# samd21_actuatorhub_Lite_TQFP32_1_1_2Feb_.net
KiCad netlist of a schematic drawn in EAGLE
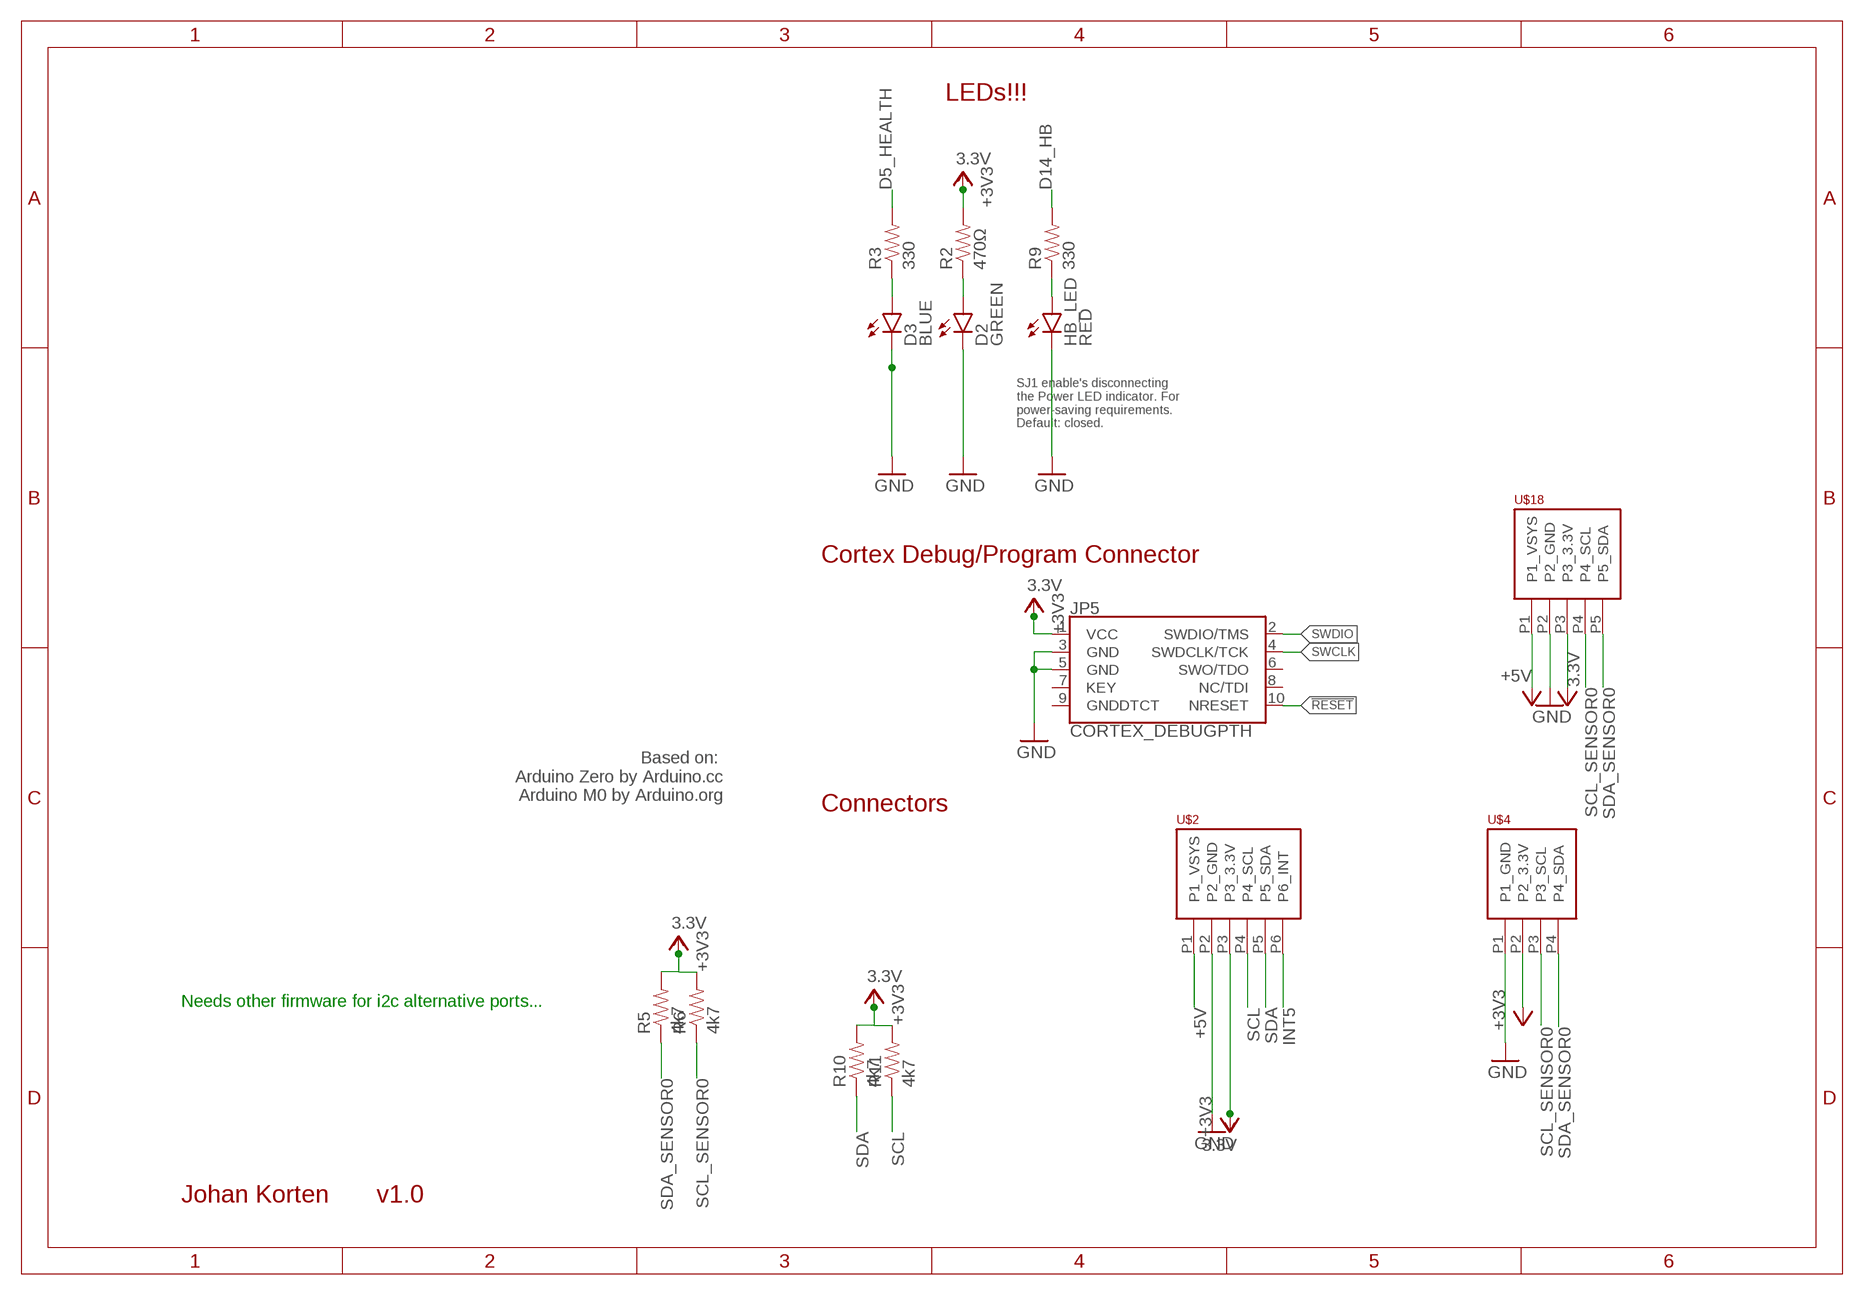
[diagram p0: schematic, sheet 1]
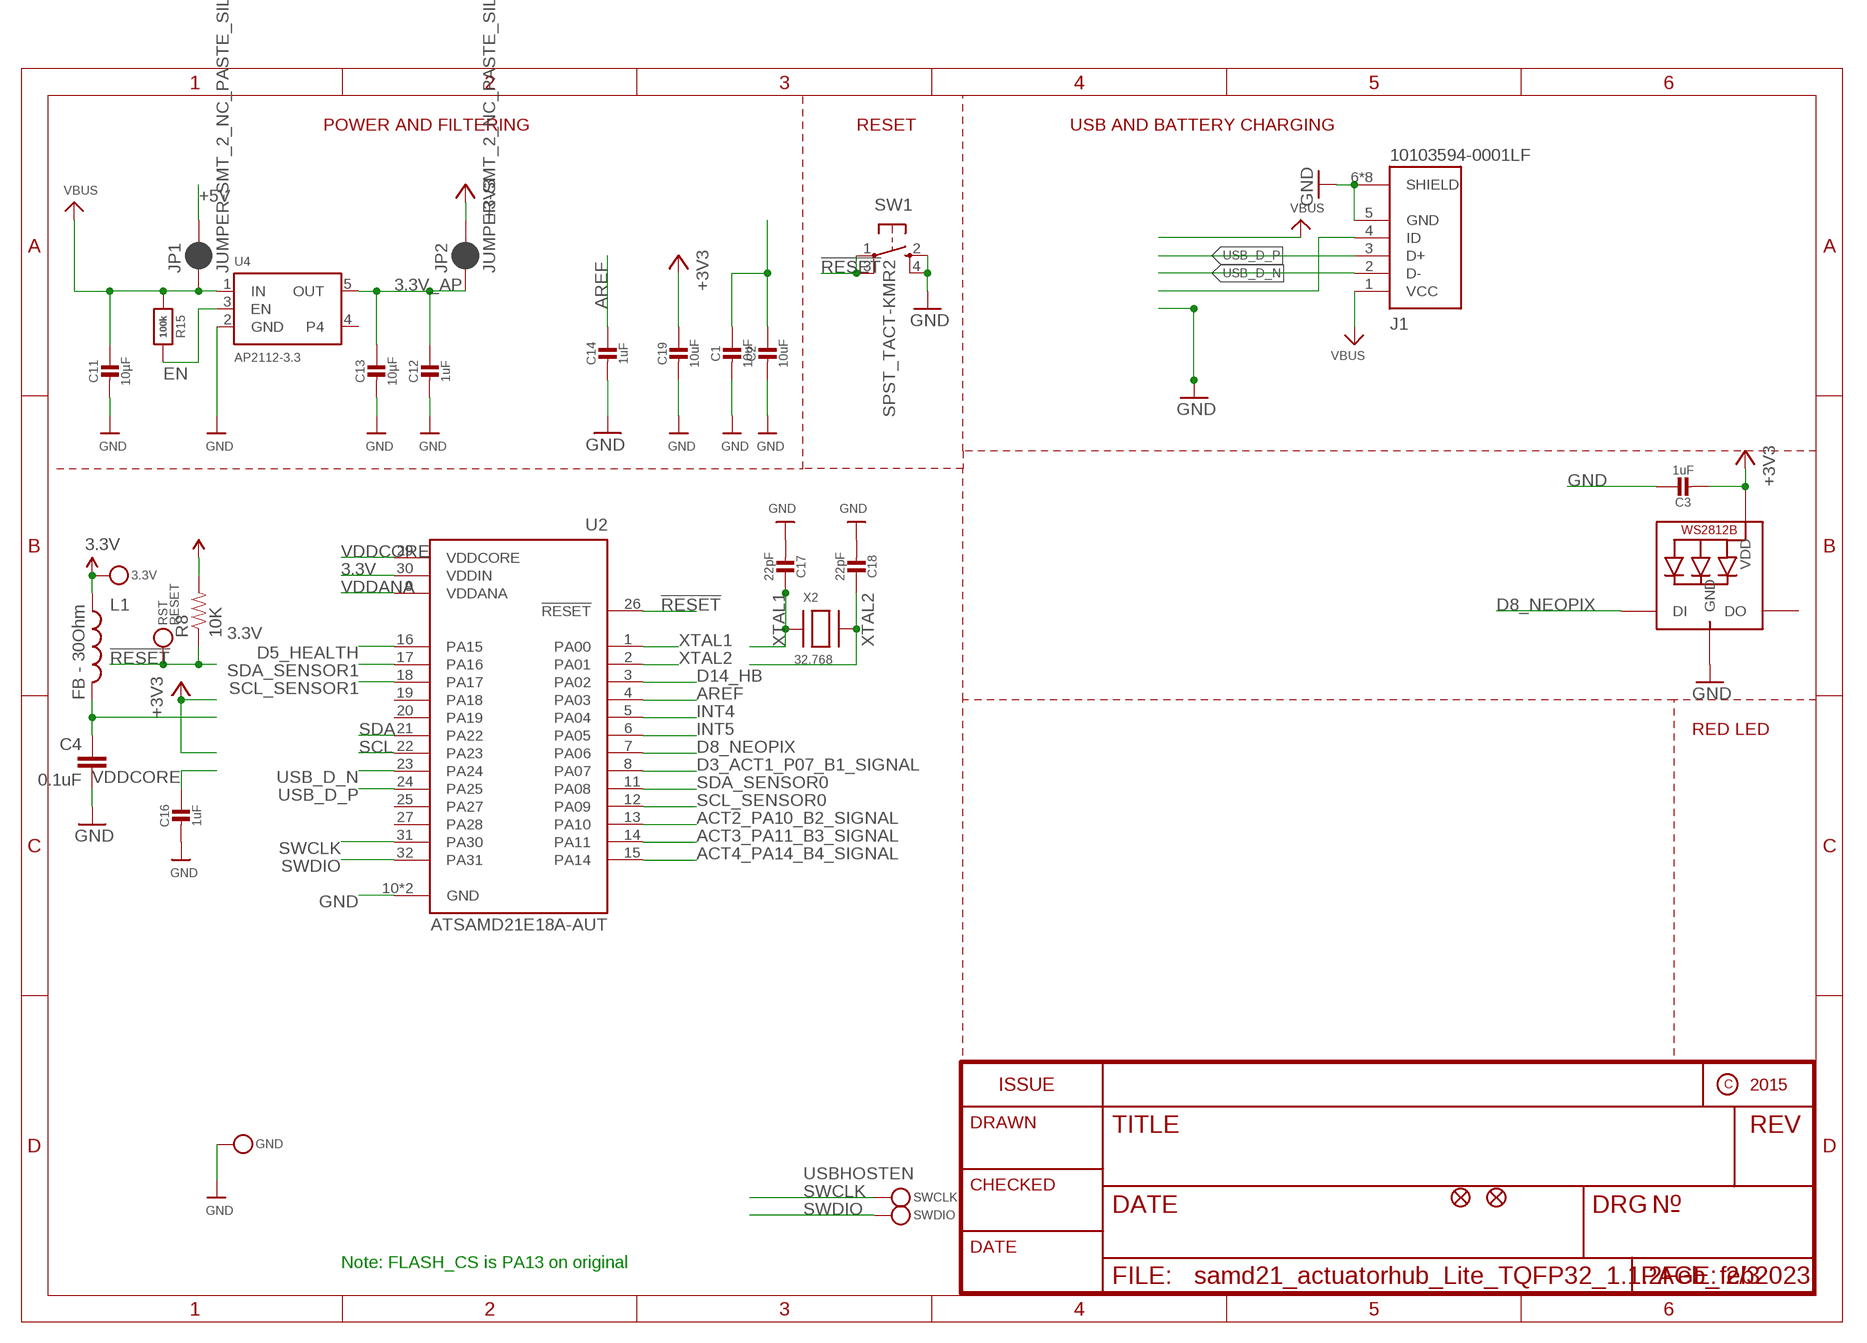
[diagram p1: schematic, sheet 2]
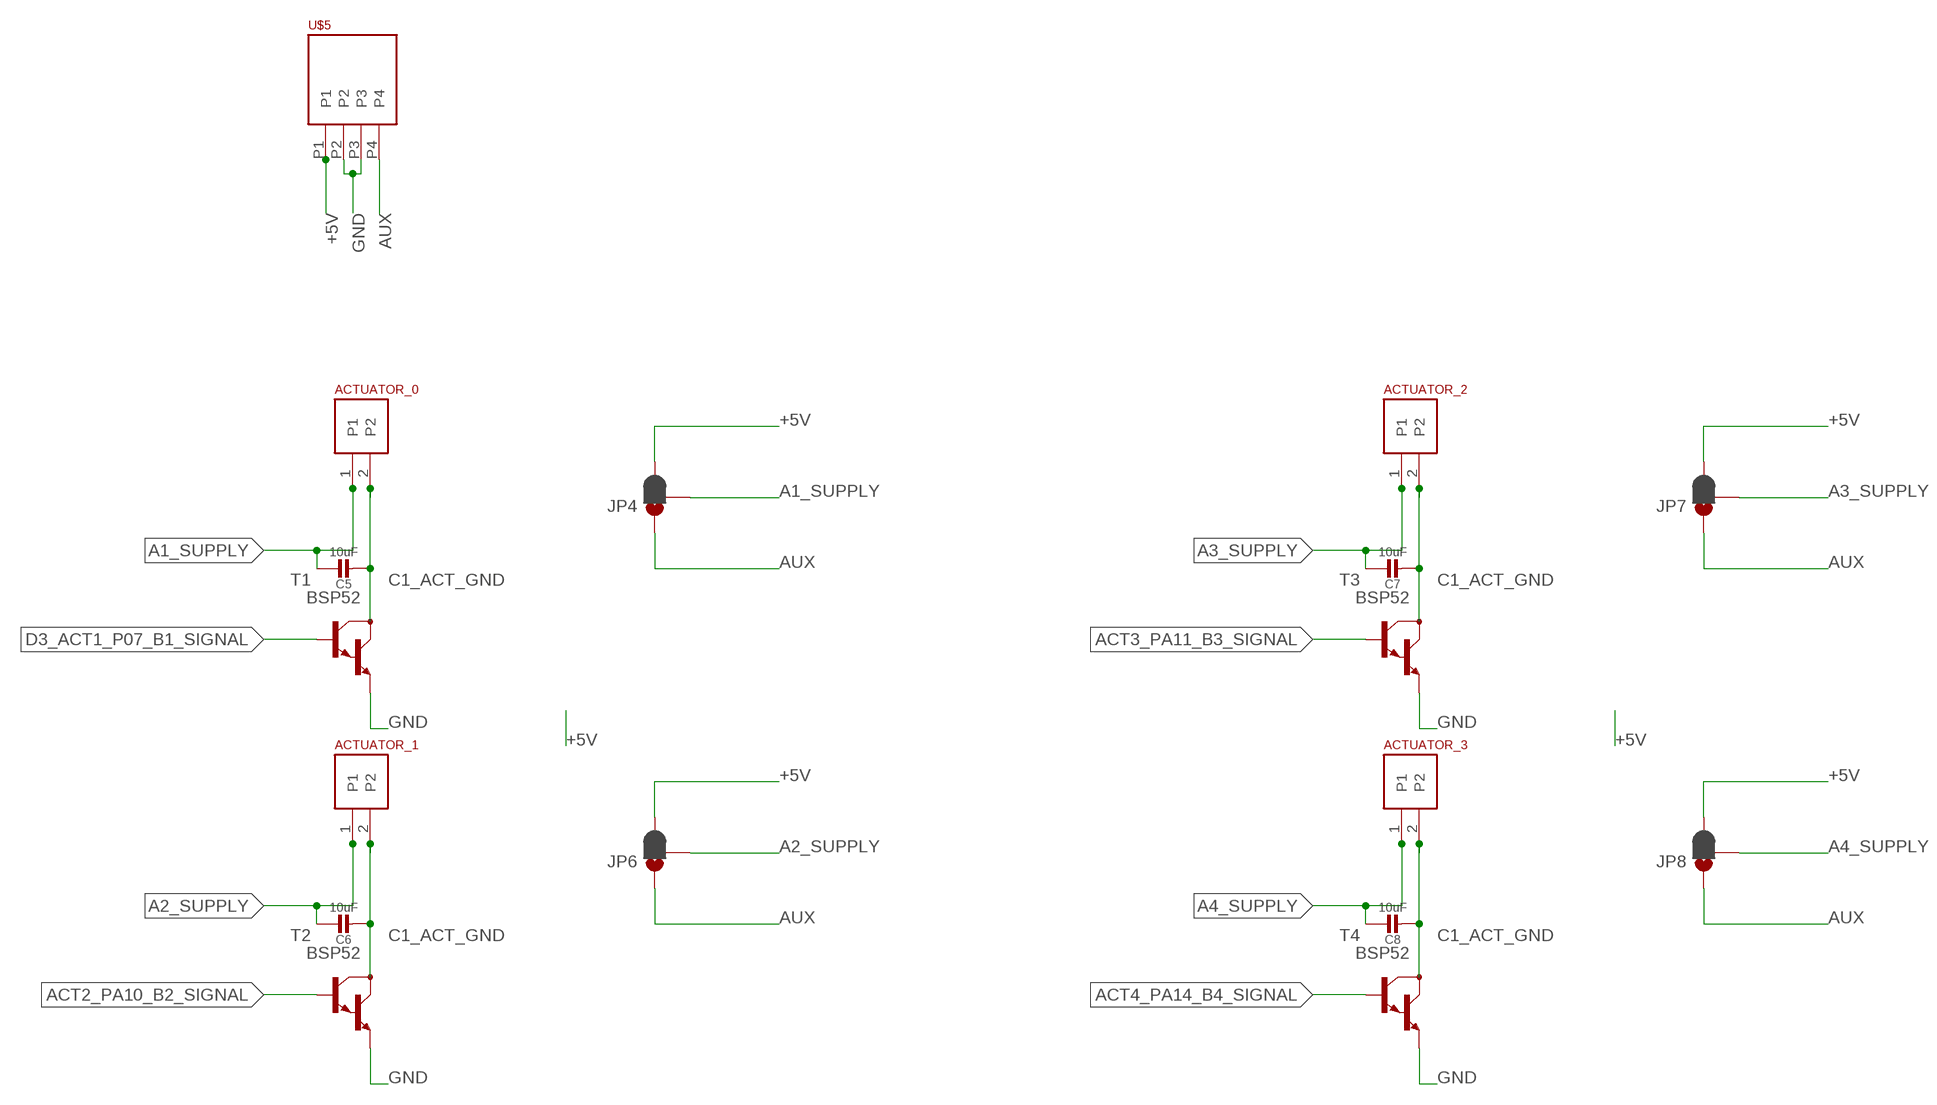
[diagram p2: schematic, sheet 3]

(export (version "E")
  (design (tool "Eeschema 10.0.6"))
  (components
    (comp (ref "ACTUATOR_0")
      (value "PHOENIX_PTSM_M2TH")
      (footprint "eagle-import:PTSM_M2_THRHOLE")
      (libsource (lib "eagle-import") (part "PHOENIX_PTSM_M2TH"))
    )
    (comp (ref "ACTUATOR_1")
      (value "PHOENIX_PTSM_M2TH")
      (footprint "eagle-import:PTSM_M2_THRHOLE")
      (libsource (lib "eagle-import") (part "PHOENIX_PTSM_M2TH"))
    )
    (comp (ref "ACTUATOR_2")
      (value "PHOENIX_PTSM_M2TH")
      (footprint "eagle-import:PTSM_M2_THRHOLE")
      (libsource (lib "eagle-import") (part "PHOENIX_PTSM_M2TH"))
    )
    (comp (ref "ACTUATOR_3")
      (value "PHOENIX_PTSM_M2TH")
      (footprint "eagle-import:PTSM_M2_THRHOLE")
      (libsource (lib "eagle-import") (part "PHOENIX_PTSM_M2TH"))
    )
    (comp (ref "C5")
      (value "10uF")
      (footprint "eagle-import:0805-NO")
      (libsource (lib "eagle-import") (part "CAP_CERAMIC0805-NOOUTLINE"))
    )
    (comp (ref "C6")
      (value "10uF")
      (footprint "eagle-import:0805-NO")
      (libsource (lib "eagle-import") (part "CAP_CERAMIC0805-NOOUTLINE"))
    )
    (comp (ref "C7")
      (value "10uF")
      (footprint "eagle-import:0805-NO")
      (libsource (lib "eagle-import") (part "CAP_CERAMIC0805-NOOUTLINE"))
    )
    (comp (ref "C8")
      (value "10uF")
      (footprint "eagle-import:0805-NO")
      (libsource (lib "eagle-import") (part "CAP_CERAMIC0805-NOOUTLINE"))
    )
    (comp (ref "JP4")
      (value "JUMPER-SMT_3_1-NC_PASTE_SILK")
      (footprint "eagle-import:SMT-JUMPER_3_1-NC_PASTE_SILK")
      (libsource (lib "eagle-import") (part "JUMPER-SMT_3_1-NC_PASTE_SILK"))
    )
    (comp (ref "JP6")
      (value "JUMPER-SMT_3_1-NC_PASTE_SILK")
      (footprint "eagle-import:SMT-JUMPER_3_1-NC_PASTE_SILK")
      (libsource (lib "eagle-import") (part "JUMPER-SMT_3_1-NC_PASTE_SILK"))
    )
    (comp (ref "JP7")
      (value "JUMPER-SMT_3_1-NC_PASTE_SILK")
      (footprint "eagle-import:SMT-JUMPER_3_1-NC_PASTE_SILK")
      (libsource (lib "eagle-import") (part "JUMPER-SMT_3_1-NC_PASTE_SILK"))
    )
    (comp (ref "JP8")
      (value "JUMPER-SMT_3_1-NC_PASTE_SILK")
      (footprint "eagle-import:SMT-JUMPER_3_1-NC_PASTE_SILK")
      (libsource (lib "eagle-import") (part "JUMPER-SMT_3_1-NC_PASTE_SILK"))
    )
    (comp (ref "T1")
      (value "BSP52")
      (footprint "eagle-import:SOT-223-4")
      (fields (field (name "MF") "ON Semiconductor"))
      (libsource (lib "eagle-import") (part "BSP52"))
    )
    (comp (ref "T2")
      (value "BSP52")
      (footprint "eagle-import:SOT-223-4")
      (fields (field (name "MF") "ON Semiconductor"))
      (libsource (lib "eagle-import") (part "BSP52"))
    )
    (comp (ref "T3")
      (value "BSP52")
      (footprint "eagle-import:SOT-223-4")
      (fields (field (name "MF") "ON Semiconductor"))
      (libsource (lib "eagle-import") (part "BSP52"))
    )
    (comp (ref "T4")
      (value "BSP52")
      (footprint "eagle-import:SOT-223-4")
      (fields (field (name "MF") "ON Semiconductor"))
      (libsource (lib "eagle-import") (part "BSP52"))
    )
    (comp (ref "U$5")
      (value "PHOENIX_PTSM_M4_TH_ANGLE")
      (footprint "eagle-import:PTSM_M4_TH_ANGLE_NEUTRAL")
      (libsource (lib "eagle-import") (part "PHOENIX_PTSM_M4_TH_ANGLE"))
    )
    (comp (ref "D2")
      (value "GREEN")
      (footprint "eagle-import:LED-0603")
      (libsource (lib "eagle-import") (part "LED-RED0603"))
    )
    (comp (ref "D3")
      (value "BLUE")
      (footprint "eagle-import:LED-0603")
      (libsource (lib "eagle-import") (part "LED-BLUE0603"))
    )
    (comp (ref "HB_LED")
      (value "RED")
      (footprint "eagle-import:LED-0603")
      (libsource (lib "eagle-import") (part "LED-RED0603"))
    )
    (comp (ref "JP5")
      (value "CORTEX_DEBUGPTH")
      (footprint "eagle-import:2X5-PTH-1.27MM")
      (libsource (lib "eagle-import") (part "CORTEX_DEBUGPTH"))
    )
    (comp (ref "R2")
      (value "470Ω")
      (footprint "eagle-import:0603-RES")
      (libsource (lib "eagle-import") (part "330OHM1/10W1%(0603)"))
    )
    (comp (ref "R3")
      (value "330")
      (footprint "eagle-import:0603-RES")
      (libsource (lib "eagle-import") (part "330OHM1/10W1%(0603)"))
    )
    (comp (ref "R5")
      (value "4k7")
      (footprint "eagle-import:0603-RES")
      (libsource (lib "eagle-import") (part "330OHM1/10W1%(0603)"))
    )
    (comp (ref "R6")
      (value "4k7")
      (footprint "eagle-import:0603-RES")
      (libsource (lib "eagle-import") (part "330OHM1/10W1%(0603)"))
    )
    (comp (ref "R9")
      (value "330")
      (footprint "eagle-import:0603-RES")
      (libsource (lib "eagle-import") (part "330OHM1/10W1%(0603)"))
    )
    (comp (ref "R10")
      (value "4k7")
      (footprint "eagle-import:0603-RES")
      (libsource (lib "eagle-import") (part "330OHM1/10W1%(0603)"))
    )
    (comp (ref "R11")
      (value "4k7")
      (footprint "eagle-import:0603-RES")
      (libsource (lib "eagle-import") (part "330OHM1/10W1%(0603)"))
    )
    (comp (ref "U$2")
      (value "PHOENIX_PTSM_M6_TH_I2CPPANGLE")
      (footprint "eagle-import:PTSM_M6_THRHOLE")
      (libsource (lib "eagle-import") (part "PHOENIX_PTSM_M6_TH_I2CPPANGLE"))
    )
    (comp (ref "U$4")
      (value "PHOENIX_PTSM_M4_THANGLE")
      (footprint "eagle-import:PTSM_M4_TH")
      (libsource (lib "eagle-import") (part "PHOENIX_PTSM_M4_THANGLE"))
    )
    (comp (ref "U$18")
      (value "PHOENIX_PTSM_M5_TH_I2C++")
      (footprint "eagle-import:PTSM_M5_THRHOLE")
      (libsource (lib "eagle-import") (part "PHOENIX_PTSM_M5_TH_I2C++"))
    )
    (comp (ref "3.3V")
      (value "TESTPOINTROUND1.5MM")
      (footprint "eagle-import:TESTPOINT_ROUND_1.5MM")
      (libsource (lib "eagle-import") (part "TESTPOINTROUND1.5MM"))
    )
    (comp (ref "C1")
      (value "10uF")
      (footprint "eagle-import:0805-NO")
      (libsource (lib "eagle-import") (part "CAP_CERAMIC0805-NOOUTLINE"))
    )
    (comp (ref "C2")
      (value "10uF")
      (footprint "eagle-import:0805-NO")
      (libsource (lib "eagle-import") (part "CAP_CERAMIC0805-NOOUTLINE"))
    )
    (comp (ref "C3")
      (value "1uF")
      (footprint "eagle-import:0603-NO")
      (libsource (lib "eagle-import") (part "CAP_CERAMIC0603_NO"))
    )
    (comp (ref "C4")
      (value "0.1uF")
      (footprint "eagle-import:0402-CAP")
      (libsource (lib "eagle-import") (part "0.1UF-16V(+-10%)(0402)"))
    )
    (comp (ref "C11")
      (value "10µF")
      (footprint "eagle-import:0805-NO")
      (libsource (lib "eagle-import") (part "CAP_CERAMIC0805-NOOUTLINE"))
    )
    (comp (ref "C12")
      (value "1uF")
      (footprint "eagle-import:0603-NO")
      (libsource (lib "eagle-import") (part "CAP_CERAMIC0603_NO"))
    )
    (comp (ref "C13")
      (value "10µF")
      (footprint "eagle-import:0805-NO")
      (libsource (lib "eagle-import") (part "CAP_CERAMIC0805-NOOUTLINE"))
    )
    (comp (ref "C14")
      (value "1uF")
      (footprint "eagle-import:0603-NO")
      (libsource (lib "eagle-import") (part "CAP_CERAMIC0603_NO"))
    )
    (comp (ref "C16")
      (value "1uF")
      (footprint "eagle-import:0603-NO")
      (libsource (lib "eagle-import") (part "CAP_CERAMIC0603_NO"))
    )
    (comp (ref "C17")
      (value "22pF")
      (footprint "eagle-import:0603-NO")
      (libsource (lib "eagle-import") (part "CAP_CERAMIC0603_NO"))
    )
    (comp (ref "C18")
      (value "22pF")
      (footprint "eagle-import:0603-NO")
      (libsource (lib "eagle-import") (part "CAP_CERAMIC0603_NO"))
    )
    (comp (ref "C19")
      (value "10uF")
      (footprint "eagle-import:0805-NO")
      (libsource (lib "eagle-import") (part "CAP_CERAMIC0805-NOOUTLINE"))
    )
    (comp (ref "GND")
      (value "TESTPOINTROUND1.5MM")
      (footprint "eagle-import:TESTPOINT_ROUND_1.5MM")
      (libsource (lib "eagle-import") (part "TESTPOINTROUND1.5MM"))
    )
    (comp (ref "J1")
      (value "10103594-0001LF")
      (footprint "eagle-import:AMPHENOL_10103594-0001LF")
      (fields (field (name "MF") "AMPHENOL ICC / FCI"))
      (libsource (lib "eagle-import") (part "10103594-0001LF"))
    )
    (comp (ref "JP1")
      (value "JUMPER-SMT_2_NC_PASTE_SILK")
      (footprint "eagle-import:SMT-JUMPER_2_NC_PASTE_SILK")
      (libsource (lib "eagle-import") (part "JUMPER-SMT_2_NC_PASTE_SILK"))
    )
    (comp (ref "JP2")
      (value "JUMPER-SMT_2_NC_PASTE_SILK")
      (footprint "eagle-import:SMT-JUMPER_2_NC_PASTE_SILK")
      (libsource (lib "eagle-import") (part "JUMPER-SMT_2_NC_PASTE_SILK"))
    )
    (comp (ref "L1")
      (value "FB - 30Ohm")
      (footprint "eagle-import:0603")
      (libsource (lib "eagle-import") (part "INDUCTOR0603"))
    )
    (comp (ref "LED1")
      (value "WS2812B3535")
      (footprint "eagle-import:LED3535")
      (libsource (lib "eagle-import") (part "WS2812B3535"))
    )
    (comp (ref "R8")
      (value "10K")
      (footprint "eagle-import:0603-RES")
      (libsource (lib "eagle-import") (part "10KOHM-1/10W-1%(0603)0603"))
    )
    (comp (ref "R15")
      (value "100k")
      (footprint "eagle-import:0603-NO")
      (libsource (lib "eagle-import") (part "RESISTOR_0603_NOOUT"))
    )
    (comp (ref "RST")
      (value "RESET")
      (footprint "eagle-import:TESTPOINT_ROUND_1.5MM")
      (libsource (lib "eagle-import") (part "TESTPOINTROUND1.5MM"))
    )
    (comp (ref "SW1")
      (value "SPST_TACT-KMR2")
      (footprint "eagle-import:KMR2")
      (libsource (lib "eagle-import") (part "SPST_TACT-KMR2"))
    )
    (comp (ref "SWCLK")
      (value "TESTPOINTROUND1.5MM")
      (footprint "eagle-import:TESTPOINT_ROUND_1.5MM")
      (libsource (lib "eagle-import") (part "TESTPOINTROUND1.5MM"))
    )
    (comp (ref "SWDIO")
      (value "TESTPOINTROUND1.5MM")
      (footprint "eagle-import:TESTPOINT_ROUND_1.5MM")
      (libsource (lib "eagle-import") (part "TESTPOINTROUND1.5MM"))
    )
    (comp (ref "U$34")
      (value "FIDUCIAL\"\"")
      (footprint "eagle-import:FIDUCIAL_1MM")
      (libsource (lib "eagle-import") (part "FIDUCIAL{dblquote}{dblquote}"))
    )
    (comp (ref "U$35")
      (value "FIDUCIAL\"\"")
      (footprint "eagle-import:FIDUCIAL_1MM")
      (libsource (lib "eagle-import") (part "FIDUCIAL{dblquote}{dblquote}"))
    )
    (comp (ref "U2")
      (value "ATSAMD21E18A-AUT")
      (footprint "eagle-import:QFP80P900X900X120-32N")
      (fields (field (name "MF") "Microchip") (field (name "MP") "ATSAMD21E18A-AU"))
      (libsource (lib "eagle-import") (part "ATSAMD21E18A-AUT"))
    )
    (comp (ref "U4")
      (value "AP2112-3.3")
      (footprint "eagle-import:SOT23-5")
      (libsource (lib "eagle-import") (part "VREG_SOT23-5"))
    )
    (comp (ref "X2")
      (value "32.768")
      (footprint "eagle-import:XTAL3215")
      (libsource (lib "eagle-import") (part "XTAL-3.2X1.5"))
    )
  )
  (nets
    (net (code "1") (name "+5V") (class "Default")
      (node (ref "C1") (pin "1") (pinfunction "1_1") (pintype "passive"))
      (node (ref "C2") (pin "1") (pinfunction "1_1") (pintype "passive"))
      (node (ref "JP1") (pin "2") (pinfunction "2_2") (pintype "passive"))
      (node (ref "JP4") (pin "3") (pinfunction "3_3") (pintype "passive"))
      (node (ref "JP6") (pin "3") (pinfunction "3_3") (pintype "passive"))
      (node (ref "JP7") (pin "3") (pinfunction "3_3") (pintype "passive"))
      (node (ref "JP8") (pin "3") (pinfunction "3_3") (pintype "passive"))
      (node (ref "U$18") (pin "P1") (pinfunction "P1_VSYS_P1") (pintype "power_in"))
      (node (ref "U$2") (pin "P1") (pinfunction "P1_VSYS_P1") (pintype "power_in"))
      (node (ref "U$5") (pin "P1") (pinfunction "P1_P1") (pintype "power_in"))
    )
    (net (code "2") (name "3.3V") (class "Default")
      (node (ref "3.3V") (pin "P$1") (pinfunction "P$1_P$1") (pintype "bidirectional"))
      (node (ref "C19") (pin "1") (pinfunction "1_1") (pintype "passive"))
      (node (ref "C3") (pin "2") (pinfunction "2_2") (pintype "passive"))
      (node (ref "JP2") (pin "2") (pinfunction "2_2") (pintype "passive"))
      (node (ref "JP5") (pin "1") (pinfunction "VCC_1") (pintype "bidirectional"))
      (node (ref "L1") (pin "1") (pinfunction "1_1") (pintype "passive"))
      (node (ref "LED1") (pin "2") (pinfunction "VDD_2") (pintype "power_in"))
      (node (ref "R10") (pin "2") (pinfunction "2_2") (pintype "passive"))
      (node (ref "R11") (pin "2") (pinfunction "2_2") (pintype "passive"))
      (node (ref "R2") (pin "2") (pinfunction "2_2") (pintype "passive"))
      (node (ref "R5") (pin "2") (pinfunction "2_2") (pintype "passive"))
      (node (ref "R6") (pin "2") (pinfunction "2_2") (pintype "passive"))
      (node (ref "R8") (pin "2") (pinfunction "2_2") (pintype "passive"))
      (node (ref "U$18") (pin "P3") (pinfunction "P3_3.3V_P3") (pintype "power_in"))
      (node (ref "U$2") (pin "P3") (pinfunction "P3_3.3V_P3") (pintype "power_in"))
      (node (ref "U$4") (pin "P2") (pinfunction "P2_3.3V_P2") (pintype "power_in"))
      (node (ref "U2") (pin "30") (pinfunction "VDDIN_30") (pintype "power_in"))
    )
    (net (code "3") (name "3.3V_AP") (class "Default")
      (node (ref "C12") (pin "1") (pinfunction "1_1") (pintype "passive"))
      (node (ref "C13") (pin "1") (pinfunction "1_1") (pintype "passive"))
      (node (ref "JP2") (pin "1") (pinfunction "1_1") (pintype "passive"))
      (node (ref "U4") (pin "5") (pinfunction "OUT_5") (pintype "power_in"))
    )
    (net (code "4") (name "A1_SUPPLY") (class "Default")
      (node (ref "ACTUATOR_0") (pin "1") (pinfunction "P1_1") (pintype "bidirectional"))
      (node (ref "C5") (pin "1") (pinfunction "1_1") (pintype "passive"))
      (node (ref "JP4") (pin "2") (pinfunction "2_2") (pintype "passive"))
    )
    (net (code "5") (name "A2_SUPPLY") (class "Default")
      (node (ref "ACTUATOR_1") (pin "1") (pinfunction "P1_1") (pintype "bidirectional"))
      (node (ref "C6") (pin "1") (pinfunction "1_1") (pintype "passive"))
      (node (ref "JP6") (pin "2") (pinfunction "2_2") (pintype "passive"))
    )
    (net (code "6") (name "A3_SUPPLY") (class "Default")
      (node (ref "ACTUATOR_2") (pin "1") (pinfunction "P1_1") (pintype "bidirectional"))
      (node (ref "C7") (pin "1") (pinfunction "1_1") (pintype "passive"))
      (node (ref "JP7") (pin "2") (pinfunction "2_2") (pintype "passive"))
    )
    (net (code "7") (name "A4_SUPPLY") (class "Default")
      (node (ref "ACTUATOR_3") (pin "1") (pinfunction "P1_1") (pintype "bidirectional"))
      (node (ref "C8") (pin "1") (pinfunction "1_1") (pintype "passive"))
      (node (ref "JP8") (pin "2") (pinfunction "2_2") (pintype "passive"))
    )
    (net (code "8") (name "ACT2_PA10_B2_SIGNAL") (class "Default")
      (node (ref "T2") (pin "1") (pinfunction "B_1") (pintype "passive"))
      (node (ref "U2") (pin "13") (pinfunction "PA10_13") (pintype "bidirectional"))
    )
    (net (code "9") (name "ACT3_PA11_B3_SIGNAL") (class "Default")
      (node (ref "T3") (pin "1") (pinfunction "B_1") (pintype "passive"))
      (node (ref "U2") (pin "14") (pinfunction "PA11_14") (pintype "bidirectional"))
    )
    (net (code "10") (name "ACT4_PA14_B4_SIGNAL") (class "Default")
      (node (ref "T4") (pin "1") (pinfunction "B_1") (pintype "passive"))
      (node (ref "U2") (pin "15") (pinfunction "PA14_15") (pintype "bidirectional"))
    )
    (net (code "11") (name "AREF") (class "Default")
      (node (ref "C14") (pin "1") (pinfunction "1_1") (pintype "passive"))
      (node (ref "U2") (pin "4") (pinfunction "PA03_4") (pintype "bidirectional"))
    )
    (net (code "12") (name "AUX") (class "Default")
      (node (ref "JP4") (pin "1") (pinfunction "1_1") (pintype "passive"))
      (node (ref "JP6") (pin "1") (pinfunction "1_1") (pintype "passive"))
      (node (ref "JP7") (pin "1") (pinfunction "1_1") (pintype "passive"))
      (node (ref "JP8") (pin "1") (pinfunction "1_1") (pintype "passive"))
      (node (ref "U$5") (pin "P4") (pinfunction "P4_P4") (pintype "power_in"))
    )
    (net (code "13") (name "C1_ACT_GND") (class "Default")
      (node (ref "ACTUATOR_0") (pin "2") (pinfunction "P2_2") (pintype "bidirectional"))
      (node (ref "ACTUATOR_1") (pin "2") (pinfunction "P2_2") (pintype "bidirectional"))
      (node (ref "ACTUATOR_2") (pin "2") (pinfunction "P2_2") (pintype "bidirectional"))
      (node (ref "ACTUATOR_3") (pin "2") (pinfunction "P2_2") (pintype "bidirectional"))
      (node (ref "C5") (pin "2") (pinfunction "2_2") (pintype "passive"))
      (node (ref "C6") (pin "2") (pinfunction "2_2") (pintype "passive"))
      (node (ref "C7") (pin "2") (pinfunction "2_2") (pintype "passive"))
      (node (ref "C8") (pin "2") (pinfunction "2_2") (pintype "passive"))
      (node (ref "T1") (pin "2") (pinfunction "C_2") (pintype "passive"))
      (node (ref "T1") (pin "4") (pinfunction "C_4") (pintype "passive"))
      (node (ref "T2") (pin "2") (pinfunction "C_2") (pintype "passive"))
      (node (ref "T2") (pin "4") (pinfunction "C_4") (pintype "passive"))
      (node (ref "T3") (pin "2") (pinfunction "C_2") (pintype "passive"))
      (node (ref "T3") (pin "4") (pinfunction "C_4") (pintype "passive"))
      (node (ref "T4") (pin "2") (pinfunction "C_2") (pintype "passive"))
      (node (ref "T4") (pin "4") (pinfunction "C_4") (pintype "passive"))
    )
    (net (code "14") (name "D3_ACT1_P07_B1_SIGNAL") (class "Default")
      (node (ref "T1") (pin "1") (pinfunction "B_1") (pintype "passive"))
      (node (ref "U2") (pin "8") (pinfunction "PA07_8") (pintype "bidirectional"))
    )
    (net (code "15") (name "D5_HEALTH") (class "Default")
      (node (ref "R3") (pin "2") (pinfunction "2_2") (pintype "passive"))
      (node (ref "U2") (pin "16") (pinfunction "PA15_16") (pintype "bidirectional"))
    )
    (net (code "16") (name "D8_NEOPIX") (class "Default")
      (node (ref "LED1") (pin "1") (pinfunction "DI_1") (pintype "input"))
      (node (ref "U2") (pin "7") (pinfunction "PA06_7") (pintype "bidirectional"))
    )
    (net (code "17") (name "D14_HB") (class "Default")
      (node (ref "R9") (pin "2") (pinfunction "2_2") (pintype "passive"))
      (node (ref "U2") (pin "3") (pinfunction "PA02_3") (pintype "bidirectional"))
    )
    (net (code "18") (name "EN") (class "Default")
      (node (ref "R15") (pin "2") (pinfunction "2_2") (pintype "passive"))
      (node (ref "U4") (pin "3") (pinfunction "EN_3") (pintype "input"))
    )
    (net (code "19") (name "GND") (class "Default")
      (node (ref "C1") (pin "2") (pinfunction "2_2") (pintype "passive"))
      (node (ref "C11") (pin "2") (pinfunction "2_2") (pintype "passive"))
      (node (ref "C12") (pin "2") (pinfunction "2_2") (pintype "passive"))
      (node (ref "C13") (pin "2") (pinfunction "2_2") (pintype "passive"))
      (node (ref "C14") (pin "2") (pinfunction "2_2") (pintype "passive"))
      (node (ref "C16") (pin "2") (pinfunction "2_2") (pintype "passive"))
      (node (ref "C17") (pin "2") (pinfunction "2_2") (pintype "passive"))
      (node (ref "C18") (pin "2") (pinfunction "2_2") (pintype "passive"))
      (node (ref "C19") (pin "2") (pinfunction "2_2") (pintype "passive"))
      (node (ref "C2") (pin "2") (pinfunction "2_2") (pintype "passive"))
      (node (ref "C3") (pin "1") (pinfunction "1_1") (pintype "passive"))
      (node (ref "C4") (pin "2") (pinfunction "2_2") (pintype "passive"))
      (node (ref "D2") (pin "C") (pinfunction "C_C") (pintype "passive"))
      (node (ref "D3") (pin "C") (pinfunction "C_C") (pintype "passive"))
      (node (ref "GND") (pin "P$1") (pinfunction "P$1_P$1") (pintype "bidirectional"))
      (node (ref "HB_LED") (pin "C") (pinfunction "C_C") (pintype "passive"))
      (node (ref "J1") (pin "10") (pinfunction "SHIELD_10") (pintype "passive"))
      (node (ref "J1") (pin "11") (pinfunction "SHIELD_11") (pintype "passive"))
      (node (ref "J1") (pin "5") (pinfunction "GND_5") (pintype "power_in"))
      (node (ref "J1") (pin "6") (pinfunction "SHIELD_6") (pintype "passive"))
      (node (ref "J1") (pin "7") (pinfunction "SHIELD_7") (pintype "passive"))
      (node (ref "J1") (pin "8") (pinfunction "SHIELD_8") (pintype "passive"))
      (node (ref "J1") (pin "9") (pinfunction "SHIELD_9") (pintype "passive"))
      (node (ref "J1") (pin "S1") (pinfunction "SHIELD_S1") (pintype "passive"))
      (node (ref "J1") (pin "S2") (pinfunction "SHIELD_S2") (pintype "passive"))
      (node (ref "JP5") (pin "3") (pinfunction "GND_3") (pintype "bidirectional"))
      (node (ref "JP5") (pin "5") (pinfunction "GND_5") (pintype "bidirectional"))
      (node (ref "LED1") (pin "4") (pinfunction "GND_4") (pintype "power_in"))
      (node (ref "SW1") (pin "2") (pinfunction "S_2") (pintype "passive"))
      (node (ref "SW1") (pin "4") (pinfunction "S1_4") (pintype "passive"))
      (node (ref "T1") (pin "3") (pinfunction "E_3") (pintype "passive"))
      (node (ref "T2") (pin "3") (pinfunction "E_3") (pintype "passive"))
      (node (ref "T3") (pin "3") (pinfunction "E_3") (pintype "passive"))
      (node (ref "T4") (pin "3") (pinfunction "E_3") (pintype "passive"))
      (node (ref "U$18") (pin "P2") (pinfunction "P2_GND_P2") (pintype "power_in"))
      (node (ref "U$2") (pin "P2") (pinfunction "P2_GND_P2") (pintype "power_in"))
      (node (ref "U$4") (pin "P1") (pinfunction "P1_GND_P1") (pintype "power_in"))
      (node (ref "U$5") (pin "P2") (pinfunction "P2_P2") (pintype "power_in"))
      (node (ref "U$5") (pin "P3") (pinfunction "P3_P3") (pintype "power_in"))
      (node (ref "U2") (pin "10") (pinfunction "GND_10") (pintype "power_in"))
      (node (ref "U2") (pin "28") (pinfunction "GND_28") (pintype "power_in"))
      (node (ref "U4") (pin "2") (pinfunction "GND_2") (pintype "power_in"))
    )
    (net (code "20") (name "INT4") (class "Default")
      (node (ref "U2") (pin "5") (pinfunction "PA04_5") (pintype "bidirectional"))
    )
    (net (code "21") (name "INT5") (class "Default")
      (node (ref "U$2") (pin "P6") (pinfunction "P6_INT_P6") (pintype "power_in"))
      (node (ref "U2") (pin "6") (pinfunction "PA05_6") (pintype "bidirectional"))
    )
    (net (code "22") (name "Net-(D2-PadA)") (class "Default")
      (node (ref "D2") (pin "A") (pinfunction "A_A") (pintype "passive"))
      (node (ref "R2") (pin "1") (pinfunction "1_1") (pintype "passive"))
    )
    (net (code "23") (name "Net-(D3-PadA)") (class "Default")
      (node (ref "D3") (pin "A") (pinfunction "A_A") (pintype "passive"))
      (node (ref "R3") (pin "1") (pinfunction "1_1") (pintype "passive"))
    )
    (net (code "24") (name "Net-(HB_LED-PadA)") (class "Default")
      (node (ref "HB_LED") (pin "A") (pinfunction "A_A") (pintype "passive"))
      (node (ref "R9") (pin "1") (pinfunction "1_1") (pintype "passive"))
    )
    (net (code "25") (name "SCL") (class "Default")
      (node (ref "R11") (pin "1") (pinfunction "1_1") (pintype "passive"))
      (node (ref "U$2") (pin "P4") (pinfunction "P4_SCL_P4") (pintype "bidirectional"))
      (node (ref "U2") (pin "22") (pinfunction "PA23_22") (pintype "bidirectional"))
    )
    (net (code "26") (name "SCL_SENSOR0") (class "Default")
      (node (ref "R6") (pin "1") (pinfunction "1_1") (pintype "passive"))
      (node (ref "U$18") (pin "P4") (pinfunction "P4_SCL_P4") (pintype "bidirectional"))
      (node (ref "U$4") (pin "P3") (pinfunction "P3_SCL_P3") (pintype "bidirectional"))
      (node (ref "U2") (pin "12") (pinfunction "PA09_12") (pintype "bidirectional"))
    )
    (net (code "27") (name "SCL_SENSOR1") (class "Default")
      (node (ref "U2") (pin "18") (pinfunction "PA17_18") (pintype "bidirectional"))
    )
    (net (code "28") (name "SDA") (class "Default")
      (node (ref "R10") (pin "1") (pinfunction "1_1") (pintype "passive"))
      (node (ref "U$2") (pin "P5") (pinfunction "P5_SDA_P5") (pintype "bidirectional"))
      (node (ref "U2") (pin "21") (pinfunction "PA22_21") (pintype "bidirectional"))
    )
    (net (code "29") (name "SDA_SENSOR0") (class "Default")
      (node (ref "R5") (pin "1") (pinfunction "1_1") (pintype "passive"))
      (node (ref "U$18") (pin "P5") (pinfunction "P5_SDA_P5") (pintype "bidirectional"))
      (node (ref "U$4") (pin "P4") (pinfunction "P4_SDA_P4") (pintype "bidirectional"))
      (node (ref "U2") (pin "11") (pinfunction "PA08_11") (pintype "bidirectional"))
    )
    (net (code "30") (name "SDA_SENSOR1") (class "Default")
      (node (ref "U2") (pin "17") (pinfunction "PA16_17") (pintype "bidirectional"))
    )
    (net (code "31") (name "SWCLK") (class "Default")
      (node (ref "JP5") (pin "4") (pinfunction "SWDCLK/TCK_4") (pintype "bidirectional"))
      (node (ref "SWCLK") (pin "P$1") (pinfunction "P$1_P$1") (pintype "bidirectional"))
      (node (ref "U2") (pin "31") (pinfunction "PA30_31") (pintype "bidirectional"))
    )
    (net (code "32") (name "SWDIO") (class "Default")
      (node (ref "JP5") (pin "2") (pinfunction "SWDIO/TMS_2") (pintype "bidirectional"))
      (node (ref "SWDIO") (pin "P$1") (pinfunction "P$1_P$1") (pintype "bidirectional"))
      (node (ref "U2") (pin "32") (pinfunction "PA31_32") (pintype "bidirectional"))
    )
    (net (code "33") (name "USB_D_N") (class "Default")
      (node (ref "J1") (pin "2") (pinfunction "D-_2") (pintype "bidirectional"))
      (node (ref "U2") (pin "23") (pinfunction "PA24_23") (pintype "bidirectional"))
    )
    (net (code "34") (name "USB_D_P") (class "Default")
      (node (ref "J1") (pin "3") (pinfunction "D+_3") (pintype "bidirectional"))
      (node (ref "U2") (pin "24") (pinfunction "PA25_24") (pintype "bidirectional"))
    )
    (net (code "35") (name "VBUS") (class "Default")
      (node (ref "C11") (pin "1") (pinfunction "1_1") (pintype "passive"))
      (node (ref "J1") (pin "1") (pinfunction "VCC_1") (pintype "power_in"))
      (node (ref "JP1") (pin "1") (pinfunction "1_1") (pintype "passive"))
      (node (ref "R15") (pin "1") (pinfunction "1_1") (pintype "passive"))
      (node (ref "U4") (pin "1") (pinfunction "IN_1") (pintype "power_in"))
    )
    (net (code "36") (name "VDDANA") (class "Default")
      (node (ref "C4") (pin "1") (pinfunction "1_1") (pintype "passive"))
      (node (ref "L1") (pin "2") (pinfunction "2_2") (pintype "passive"))
      (node (ref "U2") (pin "9") (pinfunction "VDDANA_9") (pintype "power_in"))
    )
    (net (code "37") (name "VDDCORE") (class "Default")
      (node (ref "C16") (pin "1") (pinfunction "1_1") (pintype "passive"))
      (node (ref "U2") (pin "29") (pinfunction "VDDCORE_29") (pintype "power_in"))
    )
    (net (code "38") (name "XTAL1") (class "Default")
      (node (ref "C17") (pin "1") (pinfunction "1_1") (pintype "passive"))
      (node (ref "U2") (pin "1") (pinfunction "PA00_1") (pintype "bidirectional"))
      (node (ref "X2") (pin "P$1") (pinfunction "P$1_P$1") (pintype "bidirectional"))
    )
    (net (code "39") (name "XTAL2") (class "Default")
      (node (ref "C18") (pin "1") (pinfunction "1_1") (pintype "passive"))
      (node (ref "U2") (pin "2") (pinfunction "PA01_2") (pintype "bidirectional"))
      (node (ref "X2") (pin "P$2") (pinfunction "P$2_P$2") (pintype "bidirectional"))
    )
    (net (code "40") (name "unconnected-(J1-ID-Pad4)") (class "Default")
      (node (ref "J1") (pin "4") (pinfunction "ID_4") (pintype "bidirectional"))
    )
    (net (code "41") (name "unconnected-(JP5-GNDDTCT-Pad9)") (class "Default")
      (node (ref "JP5") (pin "9") (pinfunction "GNDDTCT_9") (pintype "bidirectional"))
    )
    (net (code "42") (name "unconnected-(JP5-KEY-Pad7)") (class "Default")
      (node (ref "JP5") (pin "7") (pinfunction "KEY_7") (pintype "bidirectional"))
    )
    (net (code "43") (name "unconnected-(JP5-NC{slash}TDI-Pad8)") (class "Default")
      (node (ref "JP5") (pin "8") (pinfunction "NC/TDI_8") (pintype "bidirectional"))
    )
    (net (code "44") (name "unconnected-(JP5-SWO{slash}TDO-Pad6)") (class "Default")
      (node (ref "JP5") (pin "6") (pinfunction "SWO/TDO_6") (pintype "bidirectional"))
    )
    (net (code "45") (name "unconnected-(LED1-DO-Pad3)") (class "Default")
      (node (ref "LED1") (pin "3") (pinfunction "DO_3") (pintype "output"))
    )
    (net (code "46") (name "unconnected-(U2-PA18-Pad19)") (class "Default")
      (node (ref "U2") (pin "19") (pinfunction "PA18_19") (pintype "bidirectional"))
    )
    (net (code "47") (name "unconnected-(U2-PA19-Pad20)") (class "Default")
      (node (ref "U2") (pin "20") (pinfunction "PA19_20") (pintype "bidirectional"))
    )
    (net (code "48") (name "unconnected-(U2-PA27-Pad25)") (class "Default")
      (node (ref "U2") (pin "25") (pinfunction "PA27_25") (pintype "bidirectional"))
    )
    (net (code "49") (name "unconnected-(U2-PA28-Pad27)") (class "Default")
      (node (ref "U2") (pin "27") (pinfunction "PA28_27") (pintype "bidirectional"))
    )
    (net (code "50") (name "unconnected-(U4-P4-Pad4)") (class "Default")
      (node (ref "U4") (pin "4") (pinfunction "P4_4") (pintype "bidirectional"))
    )
    (net (code "51") (name "~{RESET}") (class "Default")
      (node (ref "JP5") (pin "10") (pinfunction "NRESET_10") (pintype "bidirectional"))
      (node (ref "R8") (pin "1") (pinfunction "1_1") (pintype "passive"))
      (node (ref "RST") (pin "P$1") (pinfunction "P$1_P$1") (pintype "bidirectional"))
      (node (ref "SW1") (pin "1") (pinfunction "P_1") (pintype "passive"))
      (node (ref "SW1") (pin "3") (pinfunction "P1_3") (pintype "passive"))
      (node (ref "U2") (pin "26") (pinfunction "~{RESET}_26") (pintype "input"))
    )
  )
)
